# core09e3.net
KiCad netlist of a schematic drawn in EAGLE
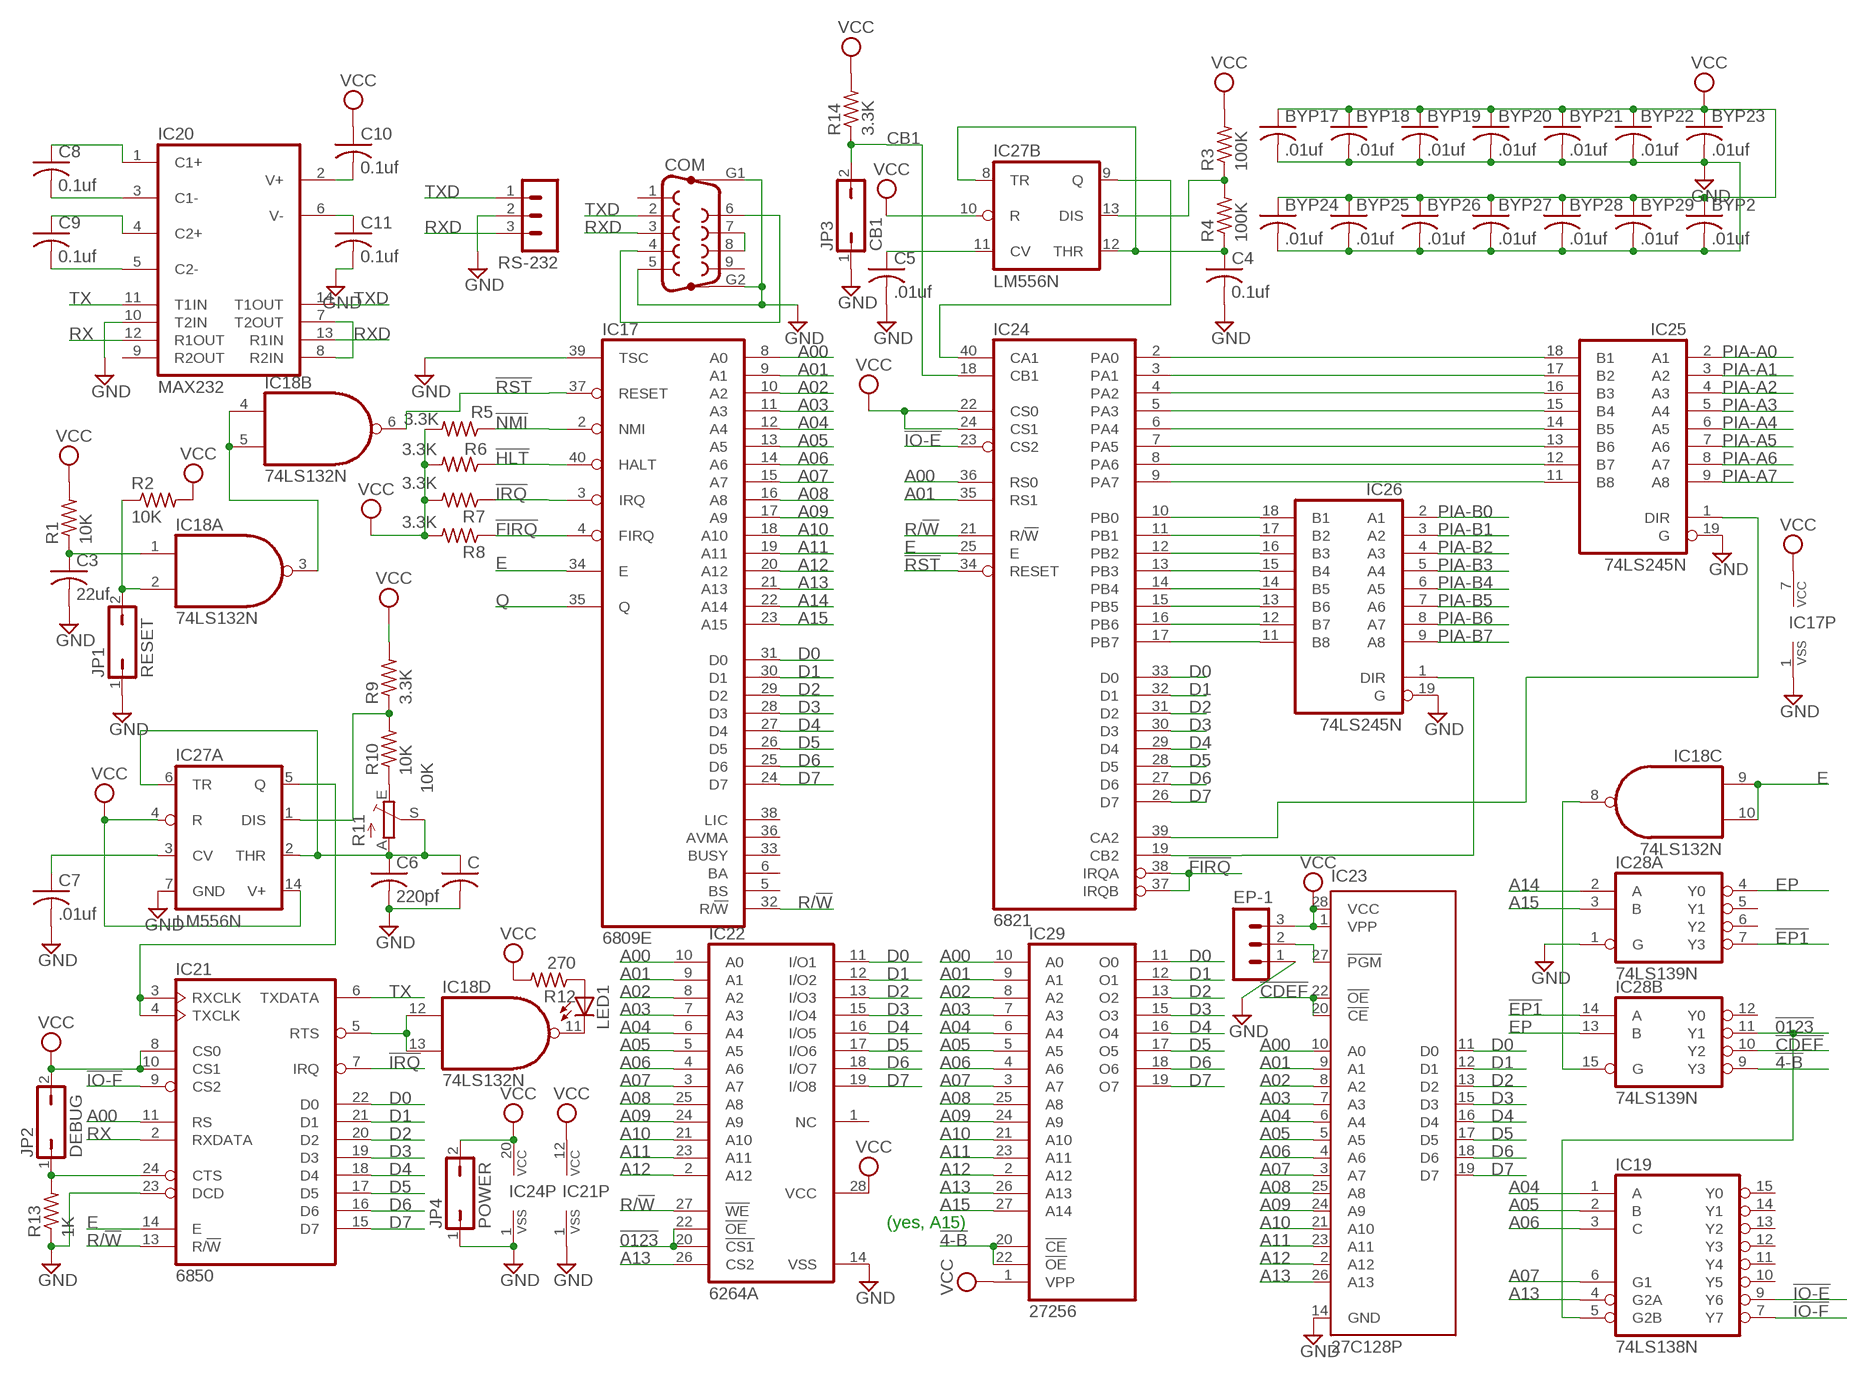
[diagram p0: schematic, sheet 1]
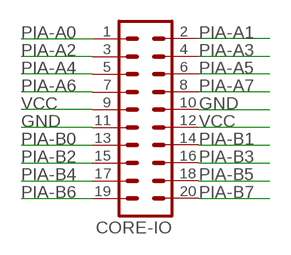
[diagram p1: schematic, sheet 2]
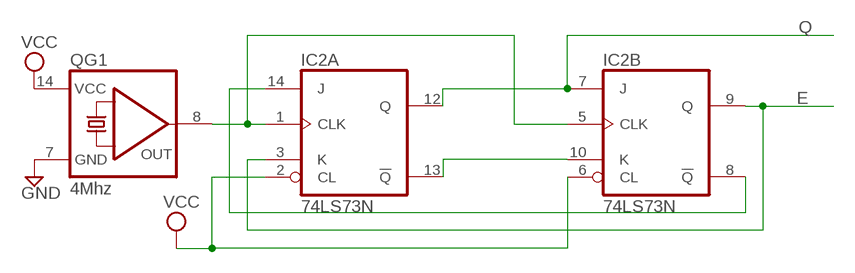
[diagram p2: schematic, sheet 3]

(export (version "E")
  (design (tool "Eeschema 10.0.6"))
  (components
    (comp (ref "CORE-IO")
      (value "MA10-2")
      (footprint "eagle-import:MA10-2")
      (libsource (lib "eagle-import") (part "MA10-2"))
    )
    (comp (ref "IC2")
      (value "74LS73N")
      (footprint "eagle-import:DIL14")
      (libsource (lib "eagle-import") (part "7473NLS"))
    )
    (comp (ref "QG1")
      (value "4Mhz")
      (footprint "eagle-import:DIL14S")
      (libsource (lib "eagle-import") (part "QG5860"))
    )
    (comp (ref "BYP2")
      (value ".01uf")
      (footprint "eagle-import:C050-025X075")
      (libsource (lib "eagle-import") (part "C-US050-025X075"))
    )
    (comp (ref "BYP17")
      (value ".01uf")
      (footprint "eagle-import:C050-025X075")
      (libsource (lib "eagle-import") (part "C-US050-025X075"))
    )
    (comp (ref "BYP18")
      (value ".01uf")
      (footprint "eagle-import:C050-025X075")
      (libsource (lib "eagle-import") (part "C-US050-025X075"))
    )
    (comp (ref "BYP19")
      (value ".01uf")
      (footprint "eagle-import:C050-025X075")
      (libsource (lib "eagle-import") (part "C-US050-025X075"))
    )
    (comp (ref "BYP20")
      (value ".01uf")
      (footprint "eagle-import:C050-025X075")
      (libsource (lib "eagle-import") (part "C-US050-025X075"))
    )
    (comp (ref "BYP21")
      (value ".01uf")
      (footprint "eagle-import:C050-025X075")
      (libsource (lib "eagle-import") (part "C-US050-025X075"))
    )
    (comp (ref "BYP22")
      (value ".01uf")
      (footprint "eagle-import:C050-025X075")
      (libsource (lib "eagle-import") (part "C-US050-025X075"))
    )
    (comp (ref "BYP23")
      (value ".01uf")
      (footprint "eagle-import:C050-025X075")
      (libsource (lib "eagle-import") (part "C-US050-025X075"))
    )
    (comp (ref "BYP24")
      (value ".01uf")
      (footprint "eagle-import:C050-025X075")
      (libsource (lib "eagle-import") (part "C-US050-025X075"))
    )
    (comp (ref "BYP25")
      (value ".01uf")
      (footprint "eagle-import:C050-025X075")
      (libsource (lib "eagle-import") (part "C-US050-025X075"))
    )
    (comp (ref "BYP26")
      (value ".01uf")
      (footprint "eagle-import:C050-025X075")
      (libsource (lib "eagle-import") (part "C-US050-025X075"))
    )
    (comp (ref "BYP27")
      (value ".01uf")
      (footprint "eagle-import:C050-025X075")
      (libsource (lib "eagle-import") (part "C-US050-025X075"))
    )
    (comp (ref "BYP28")
      (value ".01uf")
      (footprint "eagle-import:C050-025X075")
      (libsource (lib "eagle-import") (part "C-US050-025X075"))
    )
    (comp (ref "BYP29")
      (value ".01uf")
      (footprint "eagle-import:C050-025X075")
      (libsource (lib "eagle-import") (part "C-US050-025X075"))
    )
    (comp (ref "C")
      (value "C-US050-025X075")
      (footprint "eagle-import:C050-025X075")
      (libsource (lib "eagle-import") (part "C-US050-025X075"))
    )
    (comp (ref "C3")
      (value "22uf")
      (footprint "eagle-import:C102-054X133")
      (libsource (lib "eagle-import") (part "C-US102-054X133"))
    )
    (comp (ref "C4")
      (value "0.1uf")
      (footprint "eagle-import:C050-025X075")
      (libsource (lib "eagle-import") (part "C-US050-025X075"))
    )
    (comp (ref "C5")
      (value ".01uf")
      (footprint "eagle-import:C050-025X075")
      (libsource (lib "eagle-import") (part "C-US050-025X075"))
    )
    (comp (ref "C6")
      (value "220pf")
      (footprint "eagle-import:C050-025X075")
      (libsource (lib "eagle-import") (part "C-US050-025X075"))
    )
    (comp (ref "C7")
      (value ".01uf")
      (footprint "eagle-import:C050-025X075")
      (libsource (lib "eagle-import") (part "C-US050-025X075"))
    )
    (comp (ref "C8")
      (value "0.1uf")
      (footprint "eagle-import:C050-025X075")
      (libsource (lib "eagle-import") (part "C-US050-025X075"))
    )
    (comp (ref "C9")
      (value "0.1uf")
      (footprint "eagle-import:C050-025X075")
      (libsource (lib "eagle-import") (part "C-US050-025X075"))
    )
    (comp (ref "C10")
      (value "0.1uf")
      (footprint "eagle-import:C050-025X075")
      (libsource (lib "eagle-import") (part "C-US050-025X075"))
    )
    (comp (ref "C11")
      (value "0.1uf")
      (footprint "eagle-import:C050-025X075")
      (libsource (lib "eagle-import") (part "C-US050-025X075"))
    )
    (comp (ref "COM")
      (value "F09HP")
      (footprint "eagle-import:F09HP")
      (libsource (lib "eagle-import") (part "F09HP"))
    )
    (comp (ref "EP-1")
      (value "MA03-1")
      (footprint "eagle-import:MA03-1")
      (libsource (lib "eagle-import") (part "MA03-1"))
    )
    (comp (ref "IC17")
      (value "6809E")
      (footprint "eagle-import:DIL40")
      (fields (field (name "MF") "NTE ELECTRONICS") (field (name "MPN") "NTE6809E"))
      (libsource (lib "eagle-import") (part "6809E"))
    )
    (comp (ref "IC18")
      (value "74LS132N")
      (footprint "eagle-import:DIL14")
      (libsource (lib "eagle-import") (part "7400NLS"))
    )
    (comp (ref "IC19")
      (value "74LS138N")
      (footprint "eagle-import:DIL16")
      (libsource (lib "eagle-import") (part "74138NLS"))
    )
    (comp (ref "IC20")
      (value "MAX232")
      (footprint "eagle-import:DIL16")
      (fields (field (name "MF") "MAXIM") (field (name "MPN") "MAX232ACPE+"))
      (libsource (lib "eagle-import") (part "MAX232"))
    )
    (comp (ref "IC21")
      (value "6850")
      (footprint "eagle-import:DIL24")
      (fields (field (name "MF") "NTE ELECTRONICS") (field (name "MPN") "NTE6850"))
      (libsource (lib "eagle-import") (part "6850"))
    )
    (comp (ref "IC22")
      (value "6264A")
      (footprint "eagle-import:DIL28-6")
      (libsource (lib "eagle-import") (part "6264A"))
    )
    (comp (ref "IC23")
      (value "27C128P")
      (footprint "eagle-import:DIL28-6")
      (libsource (lib "eagle-import") (part "27128PC"))
    )
    (comp (ref "IC24")
      (value "6821")
      (footprint "eagle-import:DIL40")
      (fields (field (name "MF") "NTE ELECTRONICS") (field (name "MPN") "NTE6821"))
      (libsource (lib "eagle-import") (part "6821"))
    )
    (comp (ref "IC25")
      (value "74LS245N")
      (footprint "eagle-import:DIL20")
      (libsource (lib "eagle-import") (part "74245NLS"))
    )
    (comp (ref "IC26")
      (value "74LS245N")
      (footprint "eagle-import:DIL20")
      (libsource (lib "eagle-import") (part "74245NLS"))
    )
    (comp (ref "IC27")
      (value "LM556N")
      (footprint "eagle-import:DIL14")
      (libsource (lib "eagle-import") (part "556NLM"))
    )
    (comp (ref "IC28")
      (value "74LS139N")
      (footprint "eagle-import:DIL16")
      (libsource (lib "eagle-import") (part "74139NLS"))
    )
    (comp (ref "IC29")
      (value "27256")
      (footprint "eagle-import:DIL28")
      (libsource (lib "eagle-import") (part "27256"))
    )
    (comp (ref "JP1")
      (value "RESET")
      (footprint "eagle-import:JP1")
      (libsource (lib "eagle-import") (part "JP1Q"))
    )
    (comp (ref "JP2")
      (value "DEBUG")
      (footprint "eagle-import:JP1")
      (libsource (lib "eagle-import") (part "JP1Q"))
    )
    (comp (ref "JP3")
      (value "CB1")
      (footprint "eagle-import:JP1")
      (libsource (lib "eagle-import") (part "JP1Q"))
    )
    (comp (ref "JP4")
      (value "POWER")
      (footprint "eagle-import:JP1")
      (libsource (lib "eagle-import") (part "JP1Q"))
    )
    (comp (ref "LED1")
      (value "LED3MM")
      (footprint "eagle-import:LED3MM")
      (libsource (lib "eagle-import") (part "LED3MM"))
    )
    (comp (ref "R1")
      (value "10K")
      (footprint "eagle-import:0207_7")
      (libsource (lib "eagle-import") (part "R-US_0207/7"))
    )
    (comp (ref "R2")
      (value "10K")
      (footprint "eagle-import:0207_7")
      (libsource (lib "eagle-import") (part "R-US_0207/7"))
    )
    (comp (ref "R3")
      (value "100K")
      (footprint "eagle-import:0207_7")
      (libsource (lib "eagle-import") (part "R-US_0207/7"))
    )
    (comp (ref "R4")
      (value "100K")
      (footprint "eagle-import:0207_7")
      (libsource (lib "eagle-import") (part "R-US_0207/7"))
    )
    (comp (ref "R5")
      (value "3.3K")
      (footprint "eagle-import:0207_7")
      (libsource (lib "eagle-import") (part "R-US_0207/7"))
    )
    (comp (ref "R6")
      (value "3.3K")
      (footprint "eagle-import:0207_7")
      (libsource (lib "eagle-import") (part "R-US_0207/7"))
    )
    (comp (ref "R7")
      (value "3.3K")
      (footprint "eagle-import:0207_7")
      (libsource (lib "eagle-import") (part "R-US_0207/7"))
    )
    (comp (ref "R8")
      (value "3.3K")
      (footprint "eagle-import:0207_7")
      (libsource (lib "eagle-import") (part "R-US_0207/7"))
    )
    (comp (ref "R9")
      (value "3.3K")
      (footprint "eagle-import:0207_7")
      (libsource (lib "eagle-import") (part "R-US_0207/7"))
    )
    (comp (ref "R10")
      (value "10K")
      (footprint "eagle-import:0207_7")
      (libsource (lib "eagle-import") (part "R-US_0207/7"))
    )
    (comp (ref "R11")
      (value "10K")
      (footprint "eagle-import:SP19L")
      (libsource (lib "eagle-import") (part "TRIM_EU-B90P"))
    )
    (comp (ref "R12")
      (value "270")
      (footprint "eagle-import:0207_7")
      (libsource (lib "eagle-import") (part "R-US_0207/7"))
    )
    (comp (ref "R13")
      (value "1K")
      (footprint "eagle-import:0207_7")
      (libsource (lib "eagle-import") (part "R-US_0207/7"))
    )
    (comp (ref "R14")
      (value "3.3K")
      (footprint "eagle-import:0207_7")
      (libsource (lib "eagle-import") (part "R-US_0207/7"))
    )
    (comp (ref "RS-232")
      (value "MA03-1")
      (footprint "eagle-import:MA03-1")
      (libsource (lib "eagle-import") (part "MA03-1"))
    )
  )
  (nets
    (net (code "1") (name "A00") (class "Default")
      (node (ref "IC17") (pin "8") (pinfunction "A0_8") (pintype "tri_state"))
      (node (ref "IC21") (pin "11") (pinfunction "RS_11") (pintype "input"))
      (node (ref "IC22") (pin "10") (pinfunction "A0_10") (pintype "input"))
      (node (ref "IC23") (pin "10") (pinfunction "A0_10") (pintype "input"))
      (node (ref "IC24") (pin "36") (pinfunction "RS0_36") (pintype "input"))
      (node (ref "IC29") (pin "10") (pinfunction "A0_10") (pintype "input"))
    )
    (net (code "2") (name "A01") (class "Default")
      (node (ref "IC17") (pin "9") (pinfunction "A1_9") (pintype "tri_state"))
      (node (ref "IC22") (pin "9") (pinfunction "A1_9") (pintype "input"))
      (node (ref "IC23") (pin "9") (pinfunction "A1_9") (pintype "input"))
      (node (ref "IC24") (pin "35") (pinfunction "RS1_35") (pintype "input"))
      (node (ref "IC29") (pin "9") (pinfunction "A1_9") (pintype "input"))
    )
    (net (code "3") (name "A02") (class "Default")
      (node (ref "IC17") (pin "10") (pinfunction "A2_10") (pintype "tri_state"))
      (node (ref "IC22") (pin "8") (pinfunction "A2_8") (pintype "input"))
      (node (ref "IC23") (pin "8") (pinfunction "A2_8") (pintype "input"))
      (node (ref "IC29") (pin "8") (pinfunction "A2_8") (pintype "input"))
    )
    (net (code "4") (name "A03") (class "Default")
      (node (ref "IC17") (pin "11") (pinfunction "A3_11") (pintype "tri_state"))
      (node (ref "IC22") (pin "7") (pinfunction "A3_7") (pintype "input"))
      (node (ref "IC23") (pin "7") (pinfunction "A3_7") (pintype "input"))
      (node (ref "IC29") (pin "7") (pinfunction "A3_7") (pintype "input"))
    )
    (net (code "5") (name "A04") (class "Default")
      (node (ref "IC17") (pin "12") (pinfunction "A4_12") (pintype "tri_state"))
      (node (ref "IC19") (pin "1") (pinfunction "A_1") (pintype "input"))
      (node (ref "IC22") (pin "6") (pinfunction "A4_6") (pintype "input"))
      (node (ref "IC23") (pin "6") (pinfunction "A4_6") (pintype "input"))
      (node (ref "IC29") (pin "6") (pinfunction "A4_6") (pintype "input"))
    )
    (net (code "6") (name "A05") (class "Default")
      (node (ref "IC17") (pin "13") (pinfunction "A5_13") (pintype "tri_state"))
      (node (ref "IC19") (pin "2") (pinfunction "B_2") (pintype "input"))
      (node (ref "IC22") (pin "5") (pinfunction "A5_5") (pintype "input"))
      (node (ref "IC23") (pin "5") (pinfunction "A5_5") (pintype "input"))
      (node (ref "IC29") (pin "5") (pinfunction "A5_5") (pintype "input"))
    )
    (net (code "7") (name "A06") (class "Default")
      (node (ref "IC17") (pin "14") (pinfunction "A6_14") (pintype "tri_state"))
      (node (ref "IC19") (pin "3") (pinfunction "C_3") (pintype "input"))
      (node (ref "IC22") (pin "4") (pinfunction "A6_4") (pintype "input"))
      (node (ref "IC23") (pin "4") (pinfunction "A6_4") (pintype "input"))
      (node (ref "IC29") (pin "4") (pinfunction "A6_4") (pintype "input"))
    )
    (net (code "8") (name "A07") (class "Default")
      (node (ref "IC17") (pin "15") (pinfunction "A7_15") (pintype "tri_state"))
      (node (ref "IC19") (pin "6") (pinfunction "G1_6") (pintype "input"))
      (node (ref "IC22") (pin "3") (pinfunction "A7_3") (pintype "input"))
      (node (ref "IC23") (pin "3") (pinfunction "A7_3") (pintype "input"))
      (node (ref "IC29") (pin "3") (pinfunction "A7_3") (pintype "input"))
    )
    (net (code "9") (name "A08") (class "Default")
      (node (ref "IC17") (pin "16") (pinfunction "A8_16") (pintype "tri_state"))
      (node (ref "IC22") (pin "25") (pinfunction "A8_25") (pintype "input"))
      (node (ref "IC23") (pin "25") (pinfunction "A8_25") (pintype "input"))
      (node (ref "IC29") (pin "25") (pinfunction "A8_25") (pintype "input"))
    )
    (net (code "10") (name "A09") (class "Default")
      (node (ref "IC17") (pin "17") (pinfunction "A9_17") (pintype "tri_state"))
      (node (ref "IC22") (pin "24") (pinfunction "A9_24") (pintype "input"))
      (node (ref "IC23") (pin "24") (pinfunction "A9_24") (pintype "input"))
      (node (ref "IC29") (pin "24") (pinfunction "A9_24") (pintype "input"))
    )
    (net (code "11") (name "A10") (class "Default")
      (node (ref "IC17") (pin "18") (pinfunction "A10_18") (pintype "tri_state"))
      (node (ref "IC22") (pin "21") (pinfunction "A10_21") (pintype "input"))
      (node (ref "IC23") (pin "21") (pinfunction "A10_21") (pintype "input"))
      (node (ref "IC29") (pin "21") (pinfunction "A10_21") (pintype "input"))
    )
    (net (code "12") (name "A11") (class "Default")
      (node (ref "IC17") (pin "19") (pinfunction "A11_19") (pintype "tri_state"))
      (node (ref "IC22") (pin "23") (pinfunction "A11_23") (pintype "input"))
      (node (ref "IC23") (pin "23") (pinfunction "A11_23") (pintype "input"))
      (node (ref "IC29") (pin "23") (pinfunction "A11_23") (pintype "input"))
    )
    (net (code "13") (name "A12") (class "Default")
      (node (ref "IC17") (pin "20") (pinfunction "A12_20") (pintype "tri_state"))
      (node (ref "IC22") (pin "2") (pinfunction "A12_2") (pintype "input"))
      (node (ref "IC23") (pin "2") (pinfunction "A12_2") (pintype "input"))
      (node (ref "IC29") (pin "2") (pinfunction "A12_2") (pintype "input"))
    )
    (net (code "14") (name "A13") (class "Default")
      (node (ref "IC17") (pin "21") (pinfunction "A13_21") (pintype "tri_state"))
      (node (ref "IC19") (pin "4") (pinfunction "G2A_4") (pintype "input"))
      (node (ref "IC22") (pin "26") (pinfunction "CS2_26") (pintype "input"))
      (node (ref "IC23") (pin "26") (pinfunction "A13_26") (pintype "input"))
      (node (ref "IC29") (pin "26") (pinfunction "A13_26") (pintype "input"))
    )
    (net (code "15") (name "A14") (class "Default")
      (node (ref "IC17") (pin "22") (pinfunction "A14_22") (pintype "tri_state"))
      (node (ref "IC28") (pin "2") (pinfunction "A_2") (pintype "input"))
    )
    (net (code "16") (name "A15") (class "Default")
      (node (ref "IC17") (pin "23") (pinfunction "A15_23") (pintype "tri_state"))
      (node (ref "IC28") (pin "3") (pinfunction "B_3") (pintype "input"))
      (node (ref "IC29") (pin "27") (pinfunction "A14_27") (pintype "input"))
    )
    (net (code "17") (name "CB1") (class "Default")
      (node (ref "IC24") (pin "18") (pinfunction "CB1_18") (pintype "input"))
      (node (ref "JP3") (pin "2") (pinfunction "2_2") (pintype "passive"))
      (node (ref "R14") (pin "1") (pinfunction "1_1") (pintype "passive"))
    )
    (net (code "18") (name "D0") (class "Default")
      (node (ref "IC17") (pin "31") (pinfunction "D0_31") (pintype "bidirectional"))
      (node (ref "IC21") (pin "22") (pinfunction "D0_22") (pintype "bidirectional"))
      (node (ref "IC22") (pin "11") (pinfunction "I/O1_11") (pintype "bidirectional"))
      (node (ref "IC23") (pin "11") (pinfunction "D0_11") (pintype "tri_state"))
      (node (ref "IC24") (pin "33") (pinfunction "D0_33") (pintype "bidirectional"))
      (node (ref "IC29") (pin "11") (pinfunction "O0_11") (pintype "tri_state"))
    )
    (net (code "19") (name "D1") (class "Default")
      (node (ref "IC17") (pin "30") (pinfunction "D1_30") (pintype "bidirectional"))
      (node (ref "IC21") (pin "21") (pinfunction "D1_21") (pintype "bidirectional"))
      (node (ref "IC22") (pin "12") (pinfunction "I/O2_12") (pintype "bidirectional"))
      (node (ref "IC23") (pin "12") (pinfunction "D1_12") (pintype "tri_state"))
      (node (ref "IC24") (pin "32") (pinfunction "D1_32") (pintype "bidirectional"))
      (node (ref "IC29") (pin "12") (pinfunction "O1_12") (pintype "tri_state"))
    )
    (net (code "20") (name "D2") (class "Default")
      (node (ref "IC17") (pin "29") (pinfunction "D2_29") (pintype "bidirectional"))
      (node (ref "IC21") (pin "20") (pinfunction "D2_20") (pintype "bidirectional"))
      (node (ref "IC22") (pin "13") (pinfunction "I/O3_13") (pintype "bidirectional"))
      (node (ref "IC23") (pin "13") (pinfunction "D2_13") (pintype "tri_state"))
      (node (ref "IC24") (pin "31") (pinfunction "D2_31") (pintype "bidirectional"))
      (node (ref "IC29") (pin "13") (pinfunction "O2_13") (pintype "tri_state"))
    )
    (net (code "21") (name "D3") (class "Default")
      (node (ref "IC17") (pin "28") (pinfunction "D3_28") (pintype "bidirectional"))
      (node (ref "IC21") (pin "19") (pinfunction "D3_19") (pintype "bidirectional"))
      (node (ref "IC22") (pin "15") (pinfunction "I/O4_15") (pintype "bidirectional"))
      (node (ref "IC23") (pin "15") (pinfunction "D3_15") (pintype "tri_state"))
      (node (ref "IC24") (pin "30") (pinfunction "D3_30") (pintype "bidirectional"))
      (node (ref "IC29") (pin "15") (pinfunction "O3_15") (pintype "tri_state"))
    )
    (net (code "22") (name "D4") (class "Default")
      (node (ref "IC17") (pin "27") (pinfunction "D4_27") (pintype "bidirectional"))
      (node (ref "IC21") (pin "18") (pinfunction "D4_18") (pintype "bidirectional"))
      (node (ref "IC22") (pin "16") (pinfunction "I/O5_16") (pintype "bidirectional"))
      (node (ref "IC23") (pin "16") (pinfunction "D4_16") (pintype "tri_state"))
      (node (ref "IC24") (pin "29") (pinfunction "D4_29") (pintype "bidirectional"))
      (node (ref "IC29") (pin "16") (pinfunction "O4_16") (pintype "tri_state"))
    )
    (net (code "23") (name "D5") (class "Default")
      (node (ref "IC17") (pin "26") (pinfunction "D5_26") (pintype "bidirectional"))
      (node (ref "IC21") (pin "17") (pinfunction "D5_17") (pintype "bidirectional"))
      (node (ref "IC22") (pin "17") (pinfunction "I/O6_17") (pintype "bidirectional"))
      (node (ref "IC23") (pin "17") (pinfunction "D5_17") (pintype "tri_state"))
      (node (ref "IC24") (pin "28") (pinfunction "D5_28") (pintype "bidirectional"))
      (node (ref "IC29") (pin "17") (pinfunction "O5_17") (pintype "tri_state"))
    )
    (net (code "24") (name "D6") (class "Default")
      (node (ref "IC17") (pin "25") (pinfunction "D6_25") (pintype "bidirectional"))
      (node (ref "IC21") (pin "16") (pinfunction "D6_16") (pintype "bidirectional"))
      (node (ref "IC22") (pin "18") (pinfunction "I/O7_18") (pintype "bidirectional"))
      (node (ref "IC23") (pin "18") (pinfunction "D6_18") (pintype "tri_state"))
      (node (ref "IC24") (pin "27") (pinfunction "D6_27") (pintype "bidirectional"))
      (node (ref "IC29") (pin "18") (pinfunction "O6_18") (pintype "tri_state"))
    )
    (net (code "25") (name "D7") (class "Default")
      (node (ref "IC17") (pin "24") (pinfunction "D7_24") (pintype "bidirectional"))
      (node (ref "IC21") (pin "15") (pinfunction "D7_15") (pintype "bidirectional"))
      (node (ref "IC22") (pin "19") (pinfunction "I/O8_19") (pintype "bidirectional"))
      (node (ref "IC23") (pin "19") (pinfunction "D7_19") (pintype "tri_state"))
      (node (ref "IC24") (pin "26") (pinfunction "D7_26") (pintype "bidirectional"))
      (node (ref "IC29") (pin "19") (pinfunction "O7_19") (pintype "tri_state"))
    )
    (net (code "26") (name "E") (class "Default")
      (node (ref "IC17") (pin "34") (pinfunction "E_34") (pintype "input"))
      (node (ref "IC18") (pin "10") (pinfunction "I1_10") (pintype "input"))
      (node (ref "IC18") (pin "9") (pinfunction "I0_9") (pintype "input"))
      (node (ref "IC2") (pin "3") (pinfunction "K_3") (pintype "input"))
      (node (ref "IC2") (pin "9") (pinfunction "Q_9") (pintype "output"))
      (node (ref "IC21") (pin "14") (pinfunction "E_14") (pintype "input"))
      (node (ref "IC24") (pin "25") (pinfunction "E_25") (pintype "input"))
    )
    (net (code "27") (name "EP") (class "Default")
      (node (ref "IC28") (pin "13") (pinfunction "B_13") (pintype "input"))
      (node (ref "IC28") (pin "4") (pinfunction "Y0_4") (pintype "output"))
    )
    (net (code "28") (name "GND") (class "Default")
      (node (ref "BYP17") (pin "2") (pinfunction "2_2") (pintype "passive"))
      (node (ref "BYP18") (pin "2") (pinfunction "2_2") (pintype "passive"))
      (node (ref "BYP19") (pin "2") (pinfunction "2_2") (pintype "passive"))
      (node (ref "BYP2") (pin "2") (pinfunction "2_2") (pintype "passive"))
      (node (ref "BYP20") (pin "2") (pinfunction "2_2") (pintype "passive"))
      (node (ref "BYP21") (pin "2") (pinfunction "2_2") (pintype "passive"))
      (node (ref "BYP22") (pin "2") (pinfunction "2_2") (pintype "passive"))
      (node (ref "BYP23") (pin "2") (pinfunction "2_2") (pintype "passive"))
      (node (ref "BYP24") (pin "2") (pinfunction "2_2") (pintype "passive"))
      (node (ref "BYP25") (pin "2") (pinfunction "2_2") (pintype "passive"))
      (node (ref "BYP26") (pin "2") (pinfunction "2_2") (pintype "passive"))
      (node (ref "BYP27") (pin "2") (pinfunction "2_2") (pintype "passive"))
      (node (ref "BYP28") (pin "2") (pinfunction "2_2") (pintype "passive"))
      (node (ref "BYP29") (pin "2") (pinfunction "2_2") (pintype "passive"))
      (node (ref "C") (pin "2") (pinfunction "2_2") (pintype "passive"))
      (node (ref "C11") (pin "2") (pinfunction "2_2") (pintype "passive"))
      (node (ref "C3") (pin "2") (pinfunction "2_2") (pintype "passive"))
      (node (ref "C4") (pin "2") (pinfunction "2_2") (pintype "passive"))
      (node (ref "C5") (pin "2") (pinfunction "2_2") (pintype "passive"))
      (node (ref "C6") (pin "2") (pinfunction "2_2") (pintype "passive"))
      (node (ref "C7") (pin "2") (pinfunction "2_2") (pintype "passive"))
      (node (ref "COM") (pin "5") (pinfunction "5_5") (pintype "passive"))
      (node (ref "COM") (pin "G1") (pinfunction "G1_G1") (pintype "passive"))
      (node (ref "COM") (pin "G2") (pinfunction "G2_G2") (pintype "passive"))
      (node (ref "CORE-IO") (pin "10") (pinfunction "10_10") (pintype "passive"))
      (node (ref "CORE-IO") (pin "11") (pinfunction "11_11") (pintype "passive"))
      (node (ref "EP-1") (pin "1") (pinfunction "1_1") (pintype "passive"))
      (node (ref "IC17") (pin "1") (pinfunction "VSS_1") (pintype "power_in"))
      (node (ref "IC17") (pin "39") (pinfunction "TSC_39") (pintype "input"))
      (node (ref "IC20") (pin "10") (pinfunction "T2IN_10") (pintype "input"))
      (node (ref "IC21") (pin "1") (pinfunction "VSS_1") (pintype "power_in"))
      (node (ref "IC21") (pin "23") (pinfunction "DCD_23") (pintype "input"))
      (node (ref "IC22") (pin "14") (pinfunction "VSS_14") (pintype "power_in"))
      (node (ref "IC23") (pin "14") (pinfunction "GND_14") (pintype "power_in"))
      (node (ref "IC24") (pin "1") (pinfunction "VSS_1") (pintype "power_in"))
      (node (ref "IC25") (pin "19") (pinfunction "G_19") (pintype "input"))
      (node (ref "IC26") (pin "19") (pinfunction "G_19") (pintype "input"))
      (node (ref "IC27") (pin "7") (pinfunction "GND_7") (pintype "power_in"))
      (node (ref "IC28") (pin "1") (pinfunction "G_1") (pintype "input"))
      (node (ref "JP1") (pin "1") (pinfunction "1_1") (pintype "passive"))
      (node (ref "JP3") (pin "1") (pinfunction "1_1") (pintype "passive"))
      (node (ref "JP4") (pin "1") (pinfunction "1_1") (pintype "passive"))
      (node (ref "QG1") (pin "7") (pinfunction "GND_7") (pintype "power_in"))
      (node (ref "R13") (pin "1") (pinfunction "1_1") (pintype "passive"))
      (node (ref "RS-232") (pin "2") (pinfunction "2_2") (pintype "passive"))
    )
    (net (code "29") (name "Net-(COM-Pad4)") (class "Default")
      (node (ref "COM") (pin "4") (pinfunction "4_4") (pintype "passive"))
      (node (ref "COM") (pin "6") (pinfunction "6_6") (pintype "passive"))
    )
    (net (code "30") (name "Net-(COM-Pad7)") (class "Default")
      (node (ref "COM") (pin "7") (pinfunction "7_7") (pintype "passive"))
      (node (ref "COM") (pin "8") (pinfunction "8_8") (pintype "passive"))
    )
    (net (code "31") (name "Net-(IC2A-CLK)") (class "Default")
      (node (ref "IC2") (pin "1") (pinfunction "CLK_1") (pintype "input"))
      (node (ref "IC2") (pin "5") (pinfunction "CLK_5") (pintype "input"))
      (node (ref "QG1") (pin "8") (pinfunction "OUT_8") (pintype "output"))
    )
    (net (code "32") (name "Net-(IC2A-J)") (class "Default")
      (node (ref "IC2") (pin "14") (pinfunction "J_14") (pintype "input"))
      (node (ref "IC2") (pin "8") (pinfunction "~{Q}_8") (pintype "output"))
    )
    (net (code "33") (name "Net-(IC2A-~{Q})") (class "Default")
      (node (ref "IC2") (pin "10") (pinfunction "K_10") (pintype "input"))
      (node (ref "IC2") (pin "13") (pinfunction "~{Q}_13") (pintype "output"))
    )
    (net (code "34") (name "Net-(IC18A-I0)") (class "Default")
      (node (ref "C3") (pin "1") (pinfunction "1_1") (pintype "passive"))
      (node (ref "IC18") (pin "1") (pinfunction "I0_1") (pintype "input"))
      (node (ref "R1") (pin "1") (pinfunction "1_1") (pintype "passive"))
    )
    (net (code "35") (name "Net-(IC18A-I1)") (class "Default")
      (node (ref "IC18") (pin "2") (pinfunction "I1_2") (pintype "input"))
      (node (ref "JP1") (pin "2") (pinfunction "2_2") (pintype "passive"))
      (node (ref "R2") (pin "1") (pinfunction "1_1") (pintype "passive"))
    )
    (net (code "36") (name "Net-(IC18A-O)") (class "Default")
      (node (ref "IC18") (pin "3") (pinfunction "O_3") (pintype "output"))
      (node (ref "IC18") (pin "4") (pinfunction "I0_4") (pintype "input"))
      (node (ref "IC18") (pin "5") (pinfunction "I1_5") (pintype "input"))
    )
    (net (code "37") (name "Net-(IC18C-O)") (class "Default")
      (node (ref "IC18") (pin "8") (pinfunction "O_8") (pintype "output"))
      (node (ref "IC28") (pin "15") (pinfunction "G_15") (pintype "input"))
    )
    (net (code "38") (name "Net-(IC18D-I0)") (class "Default")
      (node (ref "IC18") (pin "12") (pinfunction "I0_12") (pintype "input"))
      (node (ref "IC18") (pin "13") (pinfunction "I1_13") (pintype "input"))
      (node (ref "IC21") (pin "5") (pinfunction "RTS_5") (pintype "output"))
    )
    (net (code "39") (name "Net-(IC18D-O)") (class "Default")
      (node (ref "IC18") (pin "11") (pinfunction "O_11") (pintype "output"))
      (node (ref "LED1") (pin "K") (pinfunction "C_K") (pintype "passive"))
    )
    (net (code "40") (name "Net-(IC20A-C1+)") (class "Default")
      (node (ref "C8") (pin "1") (pinfunction "1_1") (pintype "passive"))
      (node (ref "IC20") (pin "1") (pinfunction "C1+_1") (pintype "bidirectional"))
    )
    (net (code "41") (name "Net-(IC20A-C1-)") (class "Default")
      (node (ref "C8") (pin "2") (pinfunction "2_2") (pintype "passive"))
      (node (ref "IC20") (pin "3") (pinfunction "C1-_3") (pintype "bidirectional"))
    )
    (net (code "42") (name "Net-(IC20A-C2+)") (class "Default")
      (node (ref "C9") (pin "1") (pinfunction "1_1") (pintype "passive"))
      (node (ref "IC20") (pin "4") (pinfunction "C2+_4") (pintype "bidirectional"))
    )
    (net (code "43") (name "Net-(IC20A-C2-)") (class "Default")
      (node (ref "C9") (pin "2") (pinfunction "2_2") (pintype "passive"))
      (node (ref "IC20") (pin "5") (pinfunction "C2-_5") (pintype "bidirectional"))
    )
    (net (code "44") (name "Net-(IC20A-R2IN)") (class "Default")
      (node (ref "IC20") (pin "7") (pinfunction "T2OUT_7") (pintype "output"))
      (node (ref "IC20") (pin "8") (pinfunction "R2IN_8") (pintype "input"))
    )
    (net (code "45") (name "Net-(IC20A-V+)") (class "Default")
      (node (ref "C10") (pin "2") (pinfunction "2_2") (pintype "passive"))
      (node (ref "IC20") (pin "2") (pinfunction "V+_2") (pintype "bidirectional"))
    )
    (net (code "46") (name "Net-(IC20A-V-)") (class "Default")
      (node (ref "C11") (pin "1") (pinfunction "1_1") (pintype "passive"))
      (node (ref "IC20") (pin "6") (pinfunction "V-_6") (pintype "bidirectional"))
    )
    (net (code "47") (name "Net-(IC21A-CTS)") (class "Default")
      (node (ref "IC21") (pin "24") (pinfunction "CTS_24") (pintype "input"))
      (node (ref "JP2") (pin "1") (pinfunction "1_1") (pintype "passive"))
      (node (ref "R13") (pin "2") (pinfunction "2_2") (pintype "passive"))
    )
    (net (code "48") (name "Net-(IC21A-RXCLK)") (class "Default")
      (node (ref "IC21") (pin "3") (pinfunction "RXCLK_3") (pintype "input"))
      (node (ref "IC21") (pin "4") (pinfunction "TXCLK_4") (pintype "input"))
      (node (ref "IC27") (pin "5") (pinfunction "Q_5") (pintype "output"))
    )
    (net (code "49") (name "Net-(IC23-~{PGM})") (class "Default")
      (node (ref "EP-1") (pin "2") (pinfunction "2_2") (pintype "passive"))
      (node (ref "IC23") (pin "27") (pinfunction "~{PGM}_27") (pintype "passive"))
    )
    (net (code "50") (name "Net-(IC24A-CA1)") (class "Default")
      (node (ref "IC24") (pin "40") (pinfunction "CA1_40") (pintype "input"))
      (node (ref "IC27") (pin "9") (pinfunction "Q_9") (pintype "output"))
    )
    (net (code "51") (name "Net-(IC24A-CA2)") (class "Default")
      (node (ref "IC24") (pin "39") (pinfunction "CA2_39") (pintype "bidirectional"))
      (node (ref "IC25") (pin "1") (pinfunction "DIR_1") (pintype "input"))
    )
    (net (code "52") (name "Net-(IC24A-CB2)") (class "Default")
      (node (ref "IC24") (pin "19") (pinfunction "CB2_19") (pintype "bidirectional"))
      (node (ref "IC26") (pin "1") (pinfunction "DIR_1") (pintype "input"))
    )
    (net (code "53") (name "Net-(IC24A-PA0)") (class "Default")
      (node (ref "IC24") (pin "2") (pinfunction "PA0_2") (pintype "bidirectional"))
      (node (ref "IC25") (pin "18") (pinfunction "B1_18") (pintype "bidirectional"))
    )
    (net (code "54") (name "Net-(IC24A-PA1)") (class "Default")
      (node (ref "IC24") (pin "3") (pinfunction "PA1_3") (pintype "bidirectional"))
      (node (ref "IC25") (pin "17") (pinfunction "B2_17") (pintype "bidirectional"))
    )
    (net (code "55") (name "Net-(IC24A-PA2)") (class "Default")
      (node (ref "IC24") (pin "4") (pinfunction "PA2_4") (pintype "bidirectional"))
      (node (ref "IC25") (pin "16") (pinfunction "B3_16") (pintype "bidirectional"))
    )
    (net (code "56") (name "Net-(IC24A-PA3)") (class "Default")
      (node (ref "IC24") (pin "5") (pinfunction "PA3_5") (pintype "bidirectional"))
      (node (ref "IC25") (pin "15") (pinfunction "B4_15") (pintype "bidirectional"))
    )
    (net (code "57") (name "Net-(IC24A-PA4)") (class "Default")
      (node (ref "IC24") (pin "6") (pinfunction "PA4_6") (pintype "bidirectional"))
      (node (ref "IC25") (pin "14") (pinfunction "B5_14") (pintype "bidirectional"))
    )
    (net (code "58") (name "Net-(IC24A-PA5)") (class "Default")
      (node (ref "IC24") (pin "7") (pinfunction "PA5_7") (pintype "bidirectional"))
      (node (ref "IC25") (pin "13") (pinfunction "B6_13") (pintype "bidirectional"))
    )
    (net (code "59") (name "Net-(IC24A-PA6)") (class "Default")
      (node (ref "IC24") (pin "8") (pinfunction "PA6_8") (pintype "bidirectional"))
      (node (ref "IC25") (pin "12") (pinfunction "B7_12") (pintype "bidirectional"))
    )
    (net (code "60") (name "Net-(IC24A-PA7)") (class "Default")
      (node (ref "IC24") (pin "9") (pinfunction "PA7_9") (pintype "bidirectional"))
      (node (ref "IC25") (pin "11") (pinfunction "B8_11") (pintype "bidirectional"))
    )
    (net (code "61") (name "Net-(IC24A-PB0)") (class "Default")
      (node (ref "IC24") (pin "10") (pinfunction "PB0_10") (pintype "bidirectional"))
      (node (ref "IC26") (pin "18") (pinfunction "B1_18") (pintype "bidirectional"))
    )
    (net (code "62") (name "Net-(IC24A-PB1)") (class "Default")
      (node (ref "IC24") (pin "11") (pinfunction "PB1_11") (pintype "bidirectional"))
      (node (ref "IC26") (pin "17") (pinfunction "B2_17") (pintype "bidirectional"))
    )
    (net (code "63") (name "Net-(IC24A-PB2)") (class "Default")
      (node (ref "IC24") (pin "12") (pinfunction "PB2_12") (pintype "bidirectional"))
      (node (ref "IC26") (pin "16") (pinfunction "B3_16") (pintype "bidirectional"))
    )
    (net (code "64") (name "Net-(IC24A-PB3)") (class "Default")
      (node (ref "IC24") (pin "13") (pinfunction "PB3_13") (pintype "bidirectional"))
      (node (ref "IC26") (pin "15") (pinfunction "B4_15") (pintype "bidirectional"))
    )
    (net (code "65") (name "Net-(IC24A-PB4)") (class "Default")
      (node (ref "IC24") (pin "14") (pinfunction "PB4_14") (pintype "bidirectional"))
      (node (ref "IC26") (pin "14") (pinfunction "B5_14") (pintype "bidirectional"))
    )
    (net (code "66") (name "Net-(IC24A-PB5)") (class "Default")
      (node (ref "IC24") (pin "15") (pinfunction "PB5_15") (pintype "bidirectional"))
      (node (ref "IC26") (pin "13") (pinfunction "B6_13") (pintype "bidirectional"))
    )
    (net (code "67") (name "Net-(IC24A-PB6)") (class "Default")
      (node (ref "IC24") (pin "16") (pinfunction "PB6_16") (pintype "bidirectional"))
      (node (ref "IC26") (pin "12") (pinfunction "B7_12") (pintype "bidirectional"))
    )
    (net (code "68") (name "Net-(IC24A-PB7)") (class "Default")
      (node (ref "IC24") (pin "17") (pinfunction "PB7_17") (pintype "bidirectional"))
      (node (ref "IC26") (pin "11") (pinfunction "B8_11") (pintype "bidirectional"))
    )
    (net (code "69") (name "Net-(IC27A-CV)") (class "Default")
      (node (ref "C7") (pin "1") (pinfunction "1_1") (pintype "passive"))
      (node (ref "IC27") (pin "3") (pinfunction "CV_3") (pintype "input"))
    )
    (net (code "70") (name "Net-(IC27A-DIS)") (class "Default")
      (node (ref "IC27") (pin "1") (pinfunction "DIS_1") (pintype "input"))
      (node (ref "R10") (pin "2") (pinfunction "2_2") (pintype "passive"))
      (node (ref "R9") (pin "1") (pinfunction "1_1") (pintype "passive"))
    )
    (net (code "71") (name "Net-(IC27A-THR)") (class "Default")
      (node (ref "C") (pin "1") (pinfunction "1_1") (pintype "passive"))
      (node (ref "C6") (pin "1") (pinfunction "1_1") (pintype "passive"))
      (node (ref "IC27") (pin "2") (pinfunction "THR_2") (pintype "input"))
      (node (ref "IC27") (pin "6") (pinfunction "TR_6") (pintype "input"))
      (node (ref "R11") (pin "A") (pinfunction "A_A") (pintype "passive"))
      (node (ref "R11") (pin "S") (pinfunction "S_S") (pintype "passive"))
    )
    (net (code "72") (name "Net-(IC27B-CV)") (class "Default")
      (node (ref "C5") (pin "1") (pinfunction "1_1") (pintype "passive"))
      (node (ref "IC27") (pin "11") (pinfunction "CV_11") (pintype "input"))
    )
    (net (code "73") (name "Net-(IC27B-DIS)") (class "Default")
      (node (ref "IC27") (pin "13") (pinfunction "DIS_13") (pintype "input"))
      (node (ref "R3") (pin "1") (pinfunction "1_1") (pintype "passive"))
      (node (ref "R4") (pin "2") (pinfunction "2_2") (pintype "passive"))
    )
    (net (code "74") (name "Net-(IC27B-THR)") (class "Default")
      (node (ref "C4") (pin "1") (pinfunction "1_1") (pintype "passive"))
      (node (ref "IC27") (pin "12") (pinfunction "THR_12") (pintype "input"))
      (node (ref "IC27") (pin "8") (pinfunction "TR_8") (pintype "input"))
      (node (ref "R4") (pin "1") (pinfunction "1_1") (pintype "passive"))
    )
    (net (code "75") (name "Net-(LED1-PadA)") (class "Default")
      (node (ref "LED1") (pin "A") (pinfunction "A_A") (pintype "passive"))
      (node (ref "R12") (pin "1") (pinfunction "1_1") (pintype "passive"))
    )
    (net (code "76") (name "Net-(R10-Pad1)") (class "Default")
      (node (ref "R10") (pin "1") (pinfunction "1_1") (pintype "passive"))
      (node (ref "R11") (pin "E") (pinfunction "E_E") (pintype "passive"))
    )
    (net (code "77") (name "PIA-A0") (class "Default")
      (node (ref "CORE-IO") (pin "1") (pinfunction "1_1") (pintype "passive"))
      (node (ref "IC25") (pin "2") (pinfunction "A1_2") (pintype "bidirectional"))
    )
    (net (code "78") (name "PIA-A1") (class "Default")
      (node (ref "CORE-IO") (pin "2") (pinfunction "2_2") (pintype "passive"))
      (node (ref "IC25") (pin "3") (pinfunction "A2_3") (pintype "bidirectional"))
    )
    (net (code "79") (name "PIA-A2") (class "Default")
      (node (ref "CORE-IO") (pin "3") (pinfunction "3_3") (pintype "passive"))
      (node (ref "IC25") (pin "4") (pinfunction "A3_4") (pintype "bidirectional"))
    )
    (net (code "80") (name "PIA-A3") (class "Default")
      (node (ref "CORE-IO") (pin "4") (pinfunction "4_4") (pintype "passive"))
      (node (ref "IC25") (pin "5") (pinfunction "A4_5") (pintype "bidirectional"))
    )
    (net (code "81") (name "PIA-A4") (class "Default")
      (node (ref "CORE-IO") (pin "5") (pinfunction "5_5") (pintype "passive"))
      (node (ref "IC25") (pin "6") (pinfunction "A5_6") (pintype "bidirectional"))
    )
    (net (code "82") (name "PIA-A5") (class "Default")
      (node (ref "CORE-IO") (pin "6") (pinfunction "6_6") (pintype "passive"))
      (node (ref "IC25") (pin "7") (pinfunction "A6_7") (pintype "bidirectional"))
    )
    (net (code "83") (name "PIA-A6") (class "Default")
      (node (ref "CORE-IO") (pin "7") (pinfunction "7_7") (pintype "passive"))
      (node (ref "IC25") (pin "8") (pinfunction "A7_8") (pintype "bidirectional"))
    )
    (net (code "84") (name "PIA-A7") (class "Default")
      (node (ref "CORE-IO") (pin "8") (pinfunction "8_8") (pintype "passive"))
      (node (ref "IC25") (pin "9") (pinfunction "A8_9") (pintype "bidirectional"))
    )
    (net (code "85") (name "PIA-B0") (class "Default")
      (node (ref "CORE-IO") (pin "13") (pinfunction "13_13") (pintype "passive"))
      (node (ref "IC26") (pin "2") (pinfunction "A1_2") (pintype "bidirectional"))
    )
    (net (code "86") (name "PIA-B1") (class "Default")
      (node (ref "CORE-IO") (pin "14") (pinfunction "14_14") (pintype "passive"))
      (node (ref "IC26") (pin "3") (pinfunction "A2_3") (pintype "bidirectional"))
    )
    (net (code "87") (name "PIA-B2") (class "Default")
      (node (ref "CORE-IO") (pin "15") (pinfunction "15_15") (pintype "passive"))
      (node (ref "IC26") (pin "4") (pinfunction "A3_4") (pintype "bidirectional"))
    )
    (net (code "88") (name "PIA-B3") (class "Default")
      (node (ref "CORE-IO") (pin "16") (pinfunction "16_16") (pintype "passive"))
      (node (ref "IC26") (pin "5") (pinfunction "A4_5") (pintype "bidirectional"))
    )
    (net (code "89") (name "PIA-B4") (class "Default")
      (node (ref "CORE-IO") (pin "17") (pinfunction "17_17") (pintype "passive"))
      (node (ref "IC26") (pin "6") (pinfunction "A5_6") (pintype "bidirectional"))
    )
    (net (code "90") (name "PIA-B5") (class "Default")
      (node (ref "CORE-IO") (pin "18") (pinfunction "18_18") (pintype "passive"))
      (node (ref "IC26") (pin "7") (pinfunction "A6_7") (pintype "bidirectional"))
    )
    (net (code "91") (name "PIA-B6") (class "Default")
      (node (ref "CORE-IO") (pin "19") (pinfunction "19_19") (pintype "passive"))
      (node (ref "IC26") (pin "8") (pinfunction "A7_8") (pintype "bidirectional"))
    )
    (net (code "92") (name "PIA-B7") (class "Default")
      (node (ref "CORE-IO") (pin "20") (pinfunction "20_20") (pintype "passive"))
      (node (ref "IC26") (pin "9") (pinfunction "A8_9") (pintype "bidirectional"))
    )
    (net (code "93") (name "Q") (class "Default")
      (node (ref "IC17") (pin "35") (pinfunction "Q_35") (pintype "input"))
      (node (ref "IC2") (pin "12") (pinfunction "Q_12") (pintype "output"))
      (node (ref "IC2") (pin "7") (pinfunction "J_7") (pintype "input"))
    )
    (net (code "94") (name "RX") (class "Default")
      (node (ref "IC20") (pin "12") (pinfunction "R1OUT_12") (pintype "output"))
      (node (ref "IC21") (pin "2") (pinfunction "RXDATA_2") (pintype "input"))
    )
    (net (code "95") (name "RXD") (class "Default")
      (node (ref "COM") (pin "3") (pinfunction "3_3") (pintype "passive"))
      (node (ref "IC20") (pin "13") (pinfunction "R1IN_13") (pintype "input"))
      (node (ref "RS-232") (pin "3") (pinfunction "3_3") (pintype "passive"))
    )
    (net (code "96") (name "R{slash}~{W}") (class "Default")
      (node (ref "IC17") (pin "32") (pinfunction "R/~{W}_32") (pintype "output"))
      (node (ref "IC21") (pin "13") (pinfunction "R/~{W}_13") (pintype "input"))
      (node (ref "IC22") (pin "27") (pinfunction "~{WE}_27") (pintype "input"))
      (node (ref "IC24") (pin "21") (pinfunction "R/~{W}_21") (pintype "input"))
    )
    (net (code "97") (name "TX") (class "Default")
      (node (ref "IC20") (pin "11") (pinfunction "T1IN_11") (pintype "input"))
      (node (ref "IC21") (pin "6") (pinfunction "TXDATA_6") (pintype "output"))
    )
    (net (code "98") (name "TXD") (class "Default")
      (node (ref "COM") (pin "2") (pinfunction "2_2") (pintype "passive"))
      (node (ref "IC20") (pin "14") (pinfunction "T1OUT_14") (pintype "output"))
      (node (ref "RS-232") (pin "1") (pinfunction "1_1") (pintype "passive"))
    )
    (net (code "99") (name "VCC") (class "Default")
      (node (ref "BYP17") (pin "1") (pinfunction "1_1") (pintype "passive"))
      (node (ref "BYP18") (pin "1") (pinfunction "1_1") (pintype "passive"))
      (node (ref "BYP19") (pin "1") (pinfunction "1_1") (pintype "passive"))
      (node (ref "BYP2") (pin "1") (pinfunction "1_1") (pintype "passive"))
      (node (ref "BYP20") (pin "1") (pinfunction "1_1") (pintype "passive"))
      (node (ref "BYP21") (pin "1") (pinfunction "1_1") (pintype "passive"))
      (node (ref "BYP22") (pin "1") (pinfunction "1_1") (pintype "passive"))
      (node (ref "BYP23") (pin "1") (pinfunction "1_1") (pintype "passive"))
      (node (ref "BYP24") (pin "1") (pinfunction "1_1") (pintype "passive"))
      (node (ref "BYP25") (pin "1") (pinfunction "1_1") (pintype "passive"))
      (node (ref "BYP26") (pin "1") (pinfunction "1_1") (pintype "passive"))
      (node (ref "BYP27") (pin "1") (pinfunction "1_1") (pintype "passive"))
      (node (ref "BYP28") (pin "1") (pinfunction "1_1") (pintype "passive"))
      (node (ref "BYP29") (pin "1") (pinfunction "1_1") (pintype "passive"))
      (node (ref "C10") (pin "1") (pinfunction "1_1") (pintype "passive"))
      (node (ref "CORE-IO") (pin "12") (pinfunction "12_12") (pintype "passive"))
      (node (ref "CORE-IO") (pin "9") (pinfunction "9_9") (pintype "passive"))
      (node (ref "EP-1") (pin "3") (pinfunction "3_3") (pintype "passive"))
      (node (ref "IC17") (pin "7") (pinfunction "VCC_7") (pintype "power_in"))
      (node (ref "IC2") (pin "2") (pinfunction "CL_2") (pintype "input"))
      (node (ref "IC2") (pin "6") (pinfunction "CL_6") (pintype "input"))
      (node (ref "IC21") (pin "10") (pinfunction "CS1_10") (pintype "input"))
      (node (ref "IC21") (pin "12") (pinfunction "VCC_12") (pintype "power_in"))
      (node (ref "IC21") (pin "8") (pinfunction "CS0_8") (pintype "input"))
      (node (ref "IC22") (pin "28") (pinfunction "VCC_28") (pintype "power_in"))
      (node (ref "IC23") (pin "1") (pinfunction "VPP_1") (pintype "input"))
      (node (ref "IC23") (pin "28") (pinfunction "VCC_28") (pintype "power_in"))
      (node (ref "IC24") (pin "20") (pinfunction "VCC_20") (pintype "power_in"))
      (node (ref "IC24") (pin "22") (pinfunction "CS0_22") (pintype "input"))
      (node (ref "IC24") (pin "24") (pinfunction "CS1_24") (pintype "input"))
      (node (ref "IC27") (pin "10") (pinfunction "R_10") (pintype "input"))
      (node (ref "IC27") (pin "14") (pinfunction "V+_14") (pintype "power_in"))
      (node (ref "IC27") (pin "4") (pinfunction "R_4") (pintype "input"))
      (node (ref "IC29") (pin "1") (pinfunction "VPP_1") (pintype "input"))
      (node (ref "JP2") (pin "2") (pinfunction "2_2") (pintype "passive"))
      (node (ref "JP4") (pin "2") (pinfunction "2_2") (pintype "passive"))
      (node (ref "QG1") (pin "14") (pinfunction "VCC_14") (pintype "power_in"))
      (node (ref "R1") (pin "2") (pinfunction "2_2") (pintype "passive"))
      (node (ref "R12") (pin "2") (pinfunction "2_2") (pintype "passive"))
      (node (ref "R14") (pin "2") (pinfunction "2_2") (pintype "passive"))
      (node (ref "R2") (pin "2") (pinfunction "2_2") (pintype "passive"))
      (node (ref "R3") (pin "2") (pinfunction "2_2") (pintype "passive"))
      (node (ref "R5") (pin "2") (pinfunction "2_2") (pintype "passive"))
      (node (ref "R6") (pin "2") (pinfunction "2_2") (pintype "passive"))
      (node (ref "R7") (pin "2") (pinfunction "2_2") (pintype "passive"))
      (node (ref "R8") (pin "2") (pinfunction "2_2") (pintype "passive"))
      (node (ref "R9") (pin "2") (pinfunction "2_2") (pintype "passive"))
    )
    (net (code "100") (name "unconnected-(COM-Pad1)") (class "Default")
      (node (ref "COM") (pin "1") (pinfunction "1_1") (pintype "passive"))
    )
    (net (code "101") (name "unconnected-(COM-Pad9)") (class "Default")
      (node (ref "COM") (pin "9") (pinfunction "9_9") (pintype "passive"))
    )
    (net (code "102") (name "unconnected-(IC17A-AVMA-Pad36)") (class "Default")
      (node (ref "IC17") (pin "36") (pinfunction "AVMA_36") (pintype "output"))
    )
    (net (code "103") (name "unconnected-(IC17A-BA-Pad6)") (class "Default")
      (node (ref "IC17") (pin "6") (pinfunction "BA_6") (pintype "output"))
    )
    (net (code "104") (name "unconnected-(IC17A-BS-Pad5)") (class "Default")
      (node (ref "IC17") (pin "5") (pinfunction "BS_5") (pintype "output"))
    )
    (net (code "105") (name "unconnected-(IC17A-BUSY-Pad33)") (class "Default")
      (node (ref "IC17") (pin "33") (pinfunction "BUSY_33") (pintype "output"))
    )
    (net (code "106") (name "unconnected-(IC17A-LIC-Pad38)") (class "Default")
      (node (ref "IC17") (pin "38") (pinfunction "LIC_38") (pintype "output"))
    )
    (net (code "107") (name "unconnected-(IC19A-Y0-Pad15)") (class "Default")
      (node (ref "IC19") (pin "15") (pinfunction "Y0_15") (pintype "output"))
    )
    (net (code "108") (name "unconnected-(IC19A-Y1-Pad14)") (class "Default")
      (node (ref "IC19") (pin "14") (pinfunction "Y1_14") (pintype "output"))
    )
    (net (code "109") (name "unconnected-(IC19A-Y2-Pad13)") (class "Default")
      (node (ref "IC19") (pin "13") (pinfunction "Y2_13") (pintype "output"))
    )
    (net (code "110") (name "unconnected-(IC19A-Y3-Pad12)") (class "Default")
      (node (ref "IC19") (pin "12") (pinfunction "Y3_12") (pintype "output"))
    )
    (net (code "111") (name "unconnected-(IC19A-Y4-Pad11)") (class "Default")
      (node (ref "IC19") (pin "11") (pinfunction "Y4_11") (pintype "output"))
    )
    (net (code "112") (name "unconnected-(IC19A-Y5-Pad10)") (class "Default")
      (node (ref "IC19") (pin "10") (pinfunction "Y5_10") (pintype "output"))
    )
    (net (code "113") (name "unconnected-(IC20A-R2OUT-Pad9)") (class "Default")
      (node (ref "IC20") (pin "9") (pinfunction "R2OUT_9") (pintype "output"))
    )
    (net (code "114") (name "unconnected-(IC22-NC-Pad1)") (class "Default")
      (node (ref "IC22") (pin "1") (pinfunction "NC_1") (pintype "no_connect"))
    )
    (net (code "115") (name "unconnected-(IC28A-Y1-Pad5)") (class "Default")
      (node (ref "IC28") (pin "5") (pinfunction "Y1_5") (pintype "output"))
    )
    (net (code "116") (name "unconnected-(IC28A-Y2-Pad6)") (class "Default")
      (node (ref "IC28") (pin "6") (pinfunction "Y2_6") (pintype "output"))
    )
    (net (code "117") (name "unconnected-(IC28B-Y0-Pad12)") (class "Default")
      (node (ref "IC28") (pin "12") (pinfunction "Y0_12") (pintype "output"))
    )
    (net (code "118") (name "~{4-B}") (class "Default")
      (node (ref "IC28") (pin "9") (pinfunction "Y3_9") (pintype "output"))
      (node (ref "IC29") (pin "20") (pinfunction "~{CE}_20") (pintype "input"))
      (node (ref "IC29") (pin "22") (pinfunction "~{OE}_22") (pintype "input"))
    )
    (net (code "119") (name "~{0123}") (class "Default")
      (node (ref "IC19") (pin "5") (pinfunction "G2B_5") (pintype "input"))
      (node (ref "IC22") (pin "20") (pinfunction "~{CS1}_20") (pintype "input"))
      (node (ref "IC22") (pin "22") (pinfunction "~{OE}_22") (pintype "input"))
      (node (ref "IC28") (pin "11") (pinfunction "Y1_11") (pintype "output"))
    )
    (net (code "120") (name "~{CDEF}") (class "Default")
      (node (ref "IC23") (pin "20") (pinfunction "~{CE}_20") (pintype "input"))
      (node (ref "IC23") (pin "22") (pinfunction "~{OE}_22") (pintype "input"))
      (node (ref "IC28") (pin "10") (pinfunction "Y2_10") (pintype "output"))
    )
    (net (code "121") (name "~{EP1}") (class "Default")
      (node (ref "IC28") (pin "14") (pinfunction "A_14") (pintype "input"))
      (node (ref "IC28") (pin "7") (pinfunction "Y3_7") (pintype "output"))
    )
    (net (code "122") (name "~{FIRQ}") (class "Default")
      (node (ref "IC17") (pin "4") (pinfunction "FIRQ_4") (pintype "input"))
      (node (ref "IC24") (pin "37") (pinfunction "IRQB_37") (pintype "open_collector"))
      (node (ref "IC24") (pin "38") (pinfunction "IRQA_38") (pintype "open_collector"))
      (node (ref "R8") (pin "1") (pinfunction "1_1") (pintype "passive"))
    )
    (net (code "123") (name "~{HLT}") (class "Default")
      (node (ref "IC17") (pin "40") (pinfunction "HALT_40") (pintype "input"))
      (node (ref "R5") (pin "1") (pinfunction "1_1") (pintype "passive"))
    )
    (net (code "124") (name "~{IO-E}") (class "Default")
      (node (ref "IC19") (pin "9") (pinfunction "Y6_9") (pintype "output"))
      (node (ref "IC24") (pin "23") (pinfunction "CS2_23") (pintype "input"))
    )
    (net (code "125") (name "~{IO-F}") (class "Default")
      (node (ref "IC19") (pin "7") (pinfunction "Y7_7") (pintype "output"))
      (node (ref "IC21") (pin "9") (pinfunction "CS2_9") (pintype "input"))
    )
    (net (code "126") (name "~{IRQ}") (class "Default")
      (node (ref "IC17") (pin "3") (pinfunction "IRQ_3") (pintype "input"))
      (node (ref "IC21") (pin "7") (pinfunction "IRQ_7") (pintype "output"))
      (node (ref "R7") (pin "1") (pinfunction "1_1") (pintype "passive"))
    )
    (net (code "127") (name "~{NMI}") (class "Default")
      (node (ref "IC17") (pin "2") (pinfunction "NMI_2") (pintype "input"))
      (node (ref "R6") (pin "1") (pinfunction "1_1") (pintype "passive"))
    )
    (net (code "128") (name "~{RST}") (class "Default")
      (node (ref "IC17") (pin "37") (pinfunction "RESET_37") (pintype "input"))
      (node (ref "IC18") (pin "6") (pinfunction "O_6") (pintype "output"))
      (node (ref "IC24") (pin "34") (pinfunction "RESET_34") (pintype "input"))
    )
  )
)
